# RFID-Lock.net
KiCad netlist of a schematic drawn in EAGLE
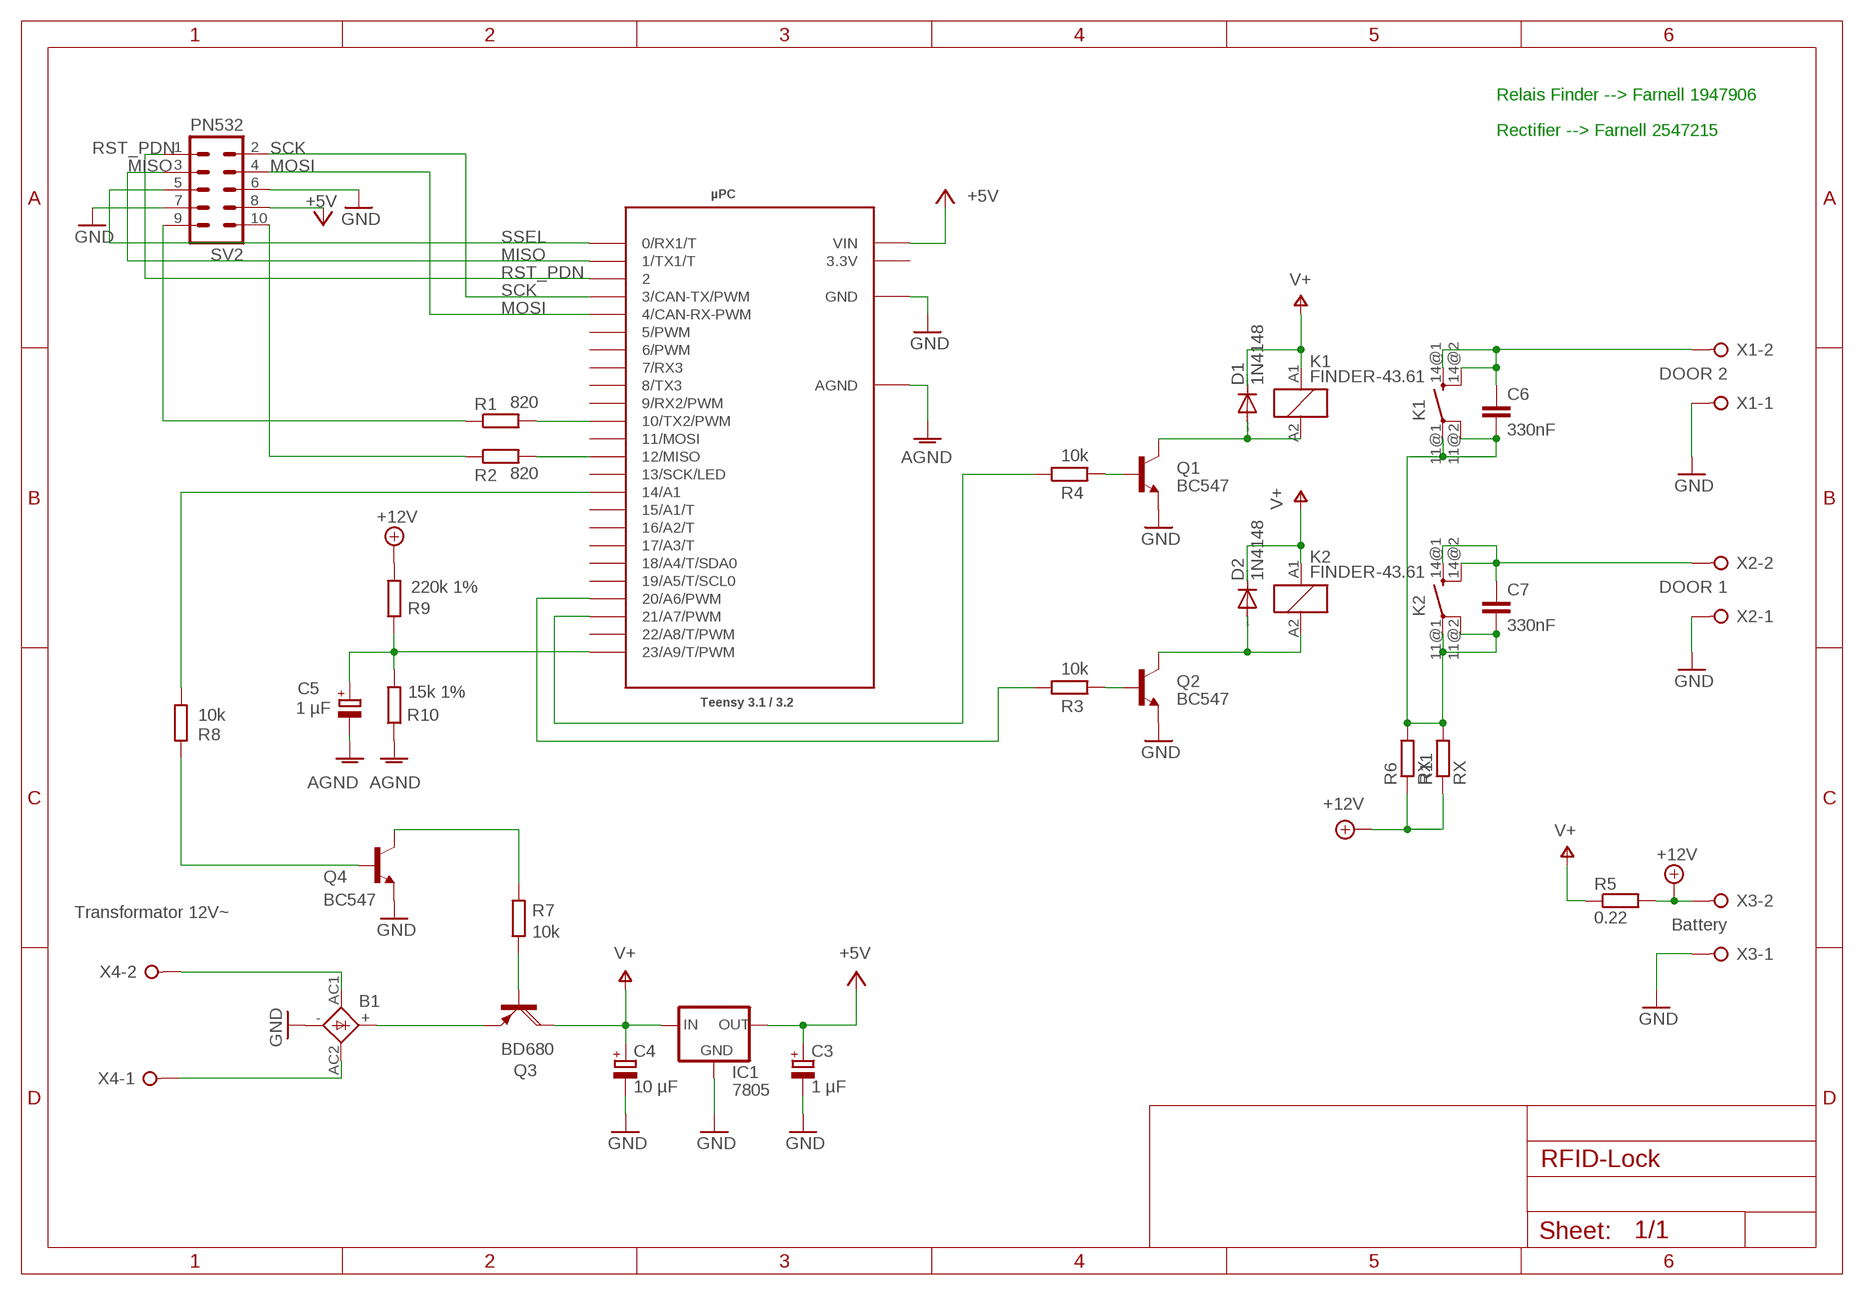
[diagram p0: schematic, sheet 1]

(export (version "E")
  (design (tool "Eeschema 10.0.6"))
  (components
    (comp (ref "B1")
      (value "GBPC6")
      (footprint "eagle-import:GBPC6")
      (libsource (lib "eagle-import") (part "GBPC6"))
    )
    (comp (ref "C3")
      (value "1 µF")
      (footprint "eagle-import:E2,5-5")
      (libsource (lib "eagle-import") (part "CPOL-EUE2.5-5"))
    )
    (comp (ref "C4")
      (value "10 µF")
      (footprint "eagle-import:E2,5-5")
      (libsource (lib "eagle-import") (part "CPOL-EUE2.5-5"))
    )
    (comp (ref "C5")
      (value "1 µF")
      (footprint "eagle-import:E2,5-5")
      (libsource (lib "eagle-import") (part "CPOL-EUE2.5-5"))
    )
    (comp (ref "C6")
      (value "330nF")
      (footprint "eagle-import:C5B4.5")
      (libsource (lib "eagle-import") (part "C5/4.5"))
    )
    (comp (ref "C7")
      (value "330nF")
      (footprint "eagle-import:C5B4.5")
      (libsource (lib "eagle-import") (part "C5/4.5"))
    )
    (comp (ref "D1")
      (value "1N4148")
      (footprint "eagle-import:DO35-7")
      (libsource (lib "eagle-import") (part "1N4148DO35-7"))
    )
    (comp (ref "D2")
      (value "1N4148")
      (footprint "eagle-import:DO35-7")
      (libsource (lib "eagle-import") (part "1N4148DO35-7"))
    )
    (comp (ref "IC1")
      (value "7805")
      (footprint "eagle-import:78XXS")
      (libsource (lib "eagle-import") (part "78XXS"))
    )
    (comp (ref "K1")
      (value "FINDER-43.61")
      (footprint "eagle-import:FINDER-43.61")
      (libsource (lib "eagle-import") (part "FINDER-43.61"))
    )
    (comp (ref "K2")
      (value "FINDER-43.61")
      (footprint "eagle-import:FINDER-43.61")
      (libsource (lib "eagle-import") (part "FINDER-43.61"))
    )
    (comp (ref "Q1")
      (value "BC547")
      (footprint "eagle-import:TO92")
      (libsource (lib "eagle-import") (part "BC547"))
    )
    (comp (ref "Q2")
      (value "BC547")
      (footprint "eagle-import:TO92")
      (libsource (lib "eagle-import") (part "BC547"))
    )
    (comp (ref "Q3")
      (value "BD680")
      (footprint "eagle-import:TO126AV")
      (libsource (lib "eagle-import") (part "BD680"))
    )
    (comp (ref "Q4")
      (value "BC547")
      (footprint "eagle-import:TO92")
      (libsource (lib "eagle-import") (part "BC547"))
    )
    (comp (ref "R1")
      (value "820")
      (footprint "eagle-import:0204_7")
      (libsource (lib "eagle-import") (part "R-EU_0204/7"))
    )
    (comp (ref "R2")
      (value "820")
      (footprint "eagle-import:0204_7")
      (libsource (lib "eagle-import") (part "R-EU_0204/7"))
    )
    (comp (ref "R3")
      (value "10k")
      (footprint "eagle-import:0204_7")
      (libsource (lib "eagle-import") (part "R-EU_0204/7"))
    )
    (comp (ref "R4")
      (value "10k")
      (footprint "eagle-import:0204_7")
      (libsource (lib "eagle-import") (part "R-EU_0204/7"))
    )
    (comp (ref "R5")
      (value "0.22")
      (footprint "eagle-import:0204_7")
      (libsource (lib "eagle-import") (part "resistor_R-EU_0204/7"))
    )
    (comp (ref "R6")
      (value "RX")
      (footprint "eagle-import:P0613_15")
      (libsource (lib "eagle-import") (part "resistor_R-EU_0613/15"))
    )
    (comp (ref "R7")
      (value "10k")
      (footprint "eagle-import:0204_7")
      (libsource (lib "eagle-import") (part "R-EU_0204/7"))
    )
    (comp (ref "R8")
      (value "10k")
      (footprint "eagle-import:0204_7")
      (libsource (lib "eagle-import") (part "R-EU_0204/7"))
    )
    (comp (ref "R9")
      (value "220k 1%")
      (footprint "eagle-import:0204_7")
      (libsource (lib "eagle-import") (part "R-EU_0204/7"))
    )
    (comp (ref "R10")
      (value "15k 1%")
      (footprint "eagle-import:0204_7")
      (libsource (lib "eagle-import") (part "R-EU_0204/7"))
    )
    (comp (ref "R11")
      (value "RX")
      (footprint "eagle-import:P0613_15")
      (libsource (lib "eagle-import") (part "resistor_R-EU_0613/15"))
    )
    (comp (ref "SV2")
      (value "PN532")
      (footprint "eagle-import:MA05-2")
      (libsource (lib "eagle-import") (part "MA05-2"))
    )
    (comp (ref "X1")
      (value "DOOR 2")
      (footprint "eagle-import:W237-132")
      (libsource (lib "eagle-import") (part "W237-02P"))
    )
    (comp (ref "X2")
      (value "DOOR 1")
      (footprint "eagle-import:W237-132")
      (libsource (lib "eagle-import") (part "W237-02P"))
    )
    (comp (ref "X3")
      (value "Battery")
      (footprint "eagle-import:W237-132")
      (libsource (lib "eagle-import") (part "W237-02P"))
    )
    (comp (ref "X4")
      (value "Transformator 12V~")
      (footprint "eagle-import:W237-132")
      (libsource (lib "eagle-import") (part "W237-02P"))
    )
    (comp (ref "µPC")
      (value "Teensy 3.1 / 3.2")
      (footprint "eagle-import:TEENSY3-DIL")
      (libsource (lib "eagle-import") (part "TEENSY_3.1_DIL"))
    )
  )
  (nets
    (net (code "1") (name "+5V") (class "Default")
      (node (ref "C3") (pin "+") (pinfunction "+_+") (pintype "passive"))
      (node (ref "IC1") (pin "OUT") (pinfunction "OUT_OUT") (pintype "passive"))
      (node (ref "SV2") (pin "8") (pinfunction "8_8") (pintype "passive"))
      (node (ref "µPC") (pin "VIN") (pinfunction "VIN_VIN") (pintype "power_in"))
    )
    (net (code "2") (name "+12V") (class "Default")
      (node (ref "R11") (pin "1") (pinfunction "1_1") (pintype "passive"))
      (node (ref "R5") (pin "2") (pinfunction "2_2") (pintype "passive"))
      (node (ref "R6") (pin "1") (pinfunction "1_1") (pintype "passive"))
      (node (ref "R9") (pin "2") (pinfunction "2_2") (pintype "passive"))
      (node (ref "X3") (pin "2") (pinfunction "KL_2") (pintype "passive"))
    )
    (net (code "3") (name "/3.3V") (class "Default")
      (node (ref "µPC") (pin "3.3V") (pinfunction "3.3V_3.3V") (pintype "power_in"))
    )
    (net (code "4") (name "/MISO") (class "Default")
      (node (ref "SV2") (pin "3") (pinfunction "3_3") (pintype "passive"))
      (node (ref "µPC") (pin "1") (pinfunction "1/TX1/T_1") (pintype "bidirectional"))
    )
    (net (code "5") (name "/MOSI") (class "Default")
      (node (ref "SV2") (pin "4") (pinfunction "4_4") (pintype "passive"))
      (node (ref "µPC") (pin "4") (pinfunction "4/CAN-RX-PWM_4") (pintype "bidirectional"))
    )
    (net (code "6") (name "/RST_PDN") (class "Default")
      (node (ref "SV2") (pin "1") (pinfunction "1_1") (pintype "passive"))
      (node (ref "µPC") (pin "2") (pinfunction "2_2") (pintype "bidirectional"))
    )
    (net (code "7") (name "/SCK") (class "Default")
      (node (ref "SV2") (pin "2") (pinfunction "2_2") (pintype "passive"))
      (node (ref "µPC") (pin "3") (pinfunction "3/CAN-TX/PWM_3") (pintype "bidirectional"))
    )
    (net (code "8") (name "/SSEL") (class "Default")
      (node (ref "SV2") (pin "5") (pinfunction "5_5") (pintype "passive"))
      (node (ref "µPC") (pin "0") (pinfunction "0/RX1/T_0") (pintype "bidirectional"))
    )
    (net (code "9") (name "AGND") (class "Default")
      (node (ref "C5") (pin "-") (pinfunction "-_-") (pintype "passive"))
      (node (ref "R10") (pin "1") (pinfunction "1_1") (pintype "passive"))
      (node (ref "µPC") (pin "AGND") (pinfunction "AGND_AGND") (pintype "power_in"))
    )
    (net (code "10") (name "GND") (class "Default")
      (node (ref "B1") (pin "-") (pinfunction "-_-") (pintype "passive"))
      (node (ref "C3") (pin "-") (pinfunction "-_-") (pintype "passive"))
      (node (ref "C4") (pin "-") (pinfunction "-_-") (pintype "passive"))
      (node (ref "IC1") (pin "GND") (pinfunction "GND_GND") (pintype "input"))
      (node (ref "Q1") (pin "1") (pinfunction "E_1") (pintype "passive"))
      (node (ref "Q2") (pin "1") (pinfunction "E_1") (pintype "passive"))
      (node (ref "Q4") (pin "1") (pinfunction "E_1") (pintype "passive"))
      (node (ref "SV2") (pin "6") (pinfunction "6_6") (pintype "passive"))
      (node (ref "SV2") (pin "7") (pinfunction "7_7") (pintype "passive"))
      (node (ref "X1") (pin "1") (pinfunction "KL_1") (pintype "passive"))
      (node (ref "X2") (pin "1") (pinfunction "KL_1") (pintype "passive"))
      (node (ref "X3") (pin "1") (pinfunction "KL_1") (pintype "passive"))
      (node (ref "µPC") (pin "GND") (pinfunction "GND_GND") (pintype "power_in"))
    )
    (net (code "11") (name "Net-(B1-Pad+)") (class "Default")
      (node (ref "B1") (pin "+") (pinfunction "+_+") (pintype "passive"))
      (node (ref "Q3") (pin "E") (pinfunction "E_E") (pintype "passive"))
    )
    (net (code "12") (name "Net-(K1A-PA)") (class "Default")
      (node (ref "C6") (pin "2") (pinfunction "2_2") (pintype "passive"))
      (node (ref "C7") (pin "2") (pinfunction "2_2") (pintype "passive"))
      (node (ref "K1") (pin "11@1") (pinfunction "PA_11@1") (pintype "passive"))
      (node (ref "K1") (pin "11@2") (pinfunction "PB_11@2") (pintype "passive"))
      (node (ref "K2") (pin "11@1") (pinfunction "PA_11@1") (pintype "passive"))
      (node (ref "K2") (pin "11@2") (pinfunction "PB_11@2") (pintype "passive"))
      (node (ref "R11") (pin "2") (pinfunction "2_2") (pintype "passive"))
      (node (ref "R6") (pin "2") (pinfunction "2_2") (pintype "passive"))
    )
    (net (code "13") (name "Net-(K1A-SA)") (class "Default")
      (node (ref "C6") (pin "1") (pinfunction "1_1") (pintype "passive"))
      (node (ref "K1") (pin "14@1") (pinfunction "SA_14@1") (pintype "passive"))
      (node (ref "K1") (pin "14@2") (pinfunction "SB_14@2") (pintype "passive"))
      (node (ref "X1") (pin "2") (pinfunction "KL_2") (pintype "passive"))
    )
    (net (code "14") (name "Net-(K1B-2)") (class "Default")
      (node (ref "D1") (pin "A") (pinfunction "A_A") (pintype "passive"))
      (node (ref "K1") (pin "A2") (pinfunction "2_A2") (pintype "passive"))
      (node (ref "Q1") (pin "3") (pinfunction "C_3") (pintype "passive"))
    )
    (net (code "15") (name "Net-(K2A-SA)") (class "Default")
      (node (ref "C7") (pin "1") (pinfunction "1_1") (pintype "passive"))
      (node (ref "K2") (pin "14@1") (pinfunction "SA_14@1") (pintype "passive"))
      (node (ref "K2") (pin "14@2") (pinfunction "SB_14@2") (pintype "passive"))
      (node (ref "X2") (pin "2") (pinfunction "KL_2") (pintype "passive"))
    )
    (net (code "16") (name "Net-(K2B-2)") (class "Default")
      (node (ref "D2") (pin "A") (pinfunction "A_A") (pintype "passive"))
      (node (ref "K2") (pin "A2") (pinfunction "2_A2") (pintype "passive"))
      (node (ref "Q2") (pin "3") (pinfunction "C_3") (pintype "passive"))
    )
    (net (code "17") (name "Net-(Q1-B)") (class "Default")
      (node (ref "Q1") (pin "2") (pinfunction "B_2") (pintype "passive"))
      (node (ref "R4") (pin "2") (pinfunction "2_2") (pintype "passive"))
    )
    (net (code "18") (name "Net-(Q2-B)") (class "Default")
      (node (ref "Q2") (pin "2") (pinfunction "B_2") (pintype "passive"))
      (node (ref "R3") (pin "2") (pinfunction "2_2") (pintype "passive"))
    )
    (net (code "19") (name "Net-(Q3-PadB)") (class "Default")
      (node (ref "Q3") (pin "B") (pinfunction "B_B") (pintype "passive"))
      (node (ref "R7") (pin "1") (pinfunction "1_1") (pintype "passive"))
    )
    (net (code "20") (name "Net-(Q4-B)") (class "Default")
      (node (ref "Q4") (pin "2") (pinfunction "B_2") (pintype "passive"))
      (node (ref "R8") (pin "1") (pinfunction "1_1") (pintype "passive"))
    )
    (net (code "21") (name "Net-(Q4-C)") (class "Default")
      (node (ref "Q4") (pin "3") (pinfunction "C_3") (pintype "passive"))
      (node (ref "R7") (pin "2") (pinfunction "2_2") (pintype "passive"))
    )
    (net (code "22") (name "Net-(R1-Pad1)") (class "Default")
      (node (ref "R1") (pin "1") (pinfunction "1_1") (pintype "passive"))
      (node (ref "SV2") (pin "9") (pinfunction "9_9") (pintype "passive"))
    )
    (net (code "23") (name "Net-(R2-Pad1)") (class "Default")
      (node (ref "R2") (pin "1") (pinfunction "1_1") (pintype "passive"))
      (node (ref "SV2") (pin "10") (pinfunction "10_10") (pintype "passive"))
    )
    (net (code "24") (name "Net-(X4A-KL)") (class "Default")
      (node (ref "B1") (pin "AC2") (pinfunction "AC2_AC2") (pintype "passive"))
      (node (ref "X4") (pin "1") (pinfunction "KL_1") (pintype "passive"))
    )
    (net (code "25") (name "Net-(X4B-KL)") (class "Default")
      (node (ref "B1") (pin "AC1") (pinfunction "AC1_AC1") (pintype "passive"))
      (node (ref "X4") (pin "2") (pinfunction "KL_2") (pintype "passive"))
    )
    (net (code "26") (name "Net-(µPC-10{slash}TX2{slash}PWM)") (class "Default")
      (node (ref "R1") (pin "2") (pinfunction "2_2") (pintype "passive"))
      (node (ref "µPC") (pin "10") (pinfunction "10/TX2/PWM_10") (pintype "bidirectional"))
    )
    (net (code "27") (name "Net-(µPC-12{slash}MISO)") (class "Default")
      (node (ref "R2") (pin "2") (pinfunction "2_2") (pintype "passive"))
      (node (ref "µPC") (pin "12") (pinfunction "12/MISO_12") (pintype "bidirectional"))
    )
    (net (code "28") (name "Net-(µPC-14{slash}A1)") (class "Default")
      (node (ref "R8") (pin "2") (pinfunction "2_2") (pintype "passive"))
      (node (ref "µPC") (pin "14/A0") (pinfunction "14/A1_14/A0") (pintype "bidirectional"))
    )
    (net (code "29") (name "Net-(µPC-20{slash}A6{slash}PWM)") (class "Default")
      (node (ref "R3") (pin "1") (pinfunction "1_1") (pintype "passive"))
      (node (ref "µPC") (pin "20/A6") (pinfunction "20/A6/PWM_20/A6") (pintype "bidirectional"))
    )
    (net (code "30") (name "Net-(µPC-21{slash}A7{slash}PWM)") (class "Default")
      (node (ref "R4") (pin "1") (pinfunction "1_1") (pintype "passive"))
      (node (ref "µPC") (pin "21/A7") (pinfunction "21/A7/PWM_21/A7") (pintype "bidirectional"))
    )
    (net (code "31") (name "Net-(µPC-23{slash}A9{slash}T{slash}PWM)") (class "Default")
      (node (ref "C5") (pin "+") (pinfunction "+_+") (pintype "passive"))
      (node (ref "R10") (pin "2") (pinfunction "2_2") (pintype "passive"))
      (node (ref "R9") (pin "1") (pinfunction "1_1") (pintype "passive"))
      (node (ref "µPC") (pin "23/A9") (pinfunction "23/A9/T/PWM_23/A9") (pintype "bidirectional"))
    )
    (net (code "32") (name "V+") (class "Default")
      (node (ref "C4") (pin "+") (pinfunction "+_+") (pintype "passive"))
      (node (ref "D1") (pin "C") (pinfunction "C_C") (pintype "passive"))
      (node (ref "D2") (pin "C") (pinfunction "C_C") (pintype "passive"))
      (node (ref "IC1") (pin "IN") (pinfunction "IN_IN") (pintype "input"))
      (node (ref "K1") (pin "A1") (pinfunction "1_A1") (pintype "passive"))
      (node (ref "K2") (pin "A1") (pinfunction "1_A1") (pintype "passive"))
      (node (ref "Q3") (pin "C") (pinfunction "C_C") (pintype "passive"))
      (node (ref "R5") (pin "1") (pinfunction "1_1") (pintype "passive"))
    )
    (net (code "33") (name "unconnected-(µPC-5{slash}PWM-Pad5)") (class "Default")
      (node (ref "µPC") (pin "5") (pinfunction "5/PWM_5") (pintype "bidirectional"))
    )
    (net (code "34") (name "unconnected-(µPC-6{slash}PWM-Pad6)") (class "Default")
      (node (ref "µPC") (pin "6") (pinfunction "6/PWM_6") (pintype "bidirectional"))
    )
    (net (code "35") (name "unconnected-(µPC-7{slash}RX3-Pad7)") (class "Default")
      (node (ref "µPC") (pin "7") (pinfunction "7/RX3_7") (pintype "bidirectional"))
    )
    (net (code "36") (name "unconnected-(µPC-8{slash}TX3-Pad8)") (class "Default")
      (node (ref "µPC") (pin "8") (pinfunction "8/TX3_8") (pintype "bidirectional"))
    )
    (net (code "37") (name "unconnected-(µPC-9{slash}RX2{slash}PWM-Pad9)") (class "Default")
      (node (ref "µPC") (pin "9") (pinfunction "9/RX2/PWM_9") (pintype "bidirectional"))
    )
    (net (code "38") (name "unconnected-(µPC-11{slash}MOSI-Pad11)") (class "Default")
      (node (ref "µPC") (pin "11") (pinfunction "11/MOSI_11") (pintype "bidirectional"))
    )
    (net (code "39") (name "unconnected-(µPC-13{slash}SCK{slash}LED-Pad13)") (class "Default")
      (node (ref "µPC") (pin "13") (pinfunction "13/SCK/LED_13") (pintype "bidirectional"))
    )
    (net (code "40") (name "unconnected-(µPC-15{slash}A1{slash}T-Pad15{slash}A1)") (class "Default")
      (node (ref "µPC") (pin "15/A1") (pinfunction "15/A1/T_15/A1") (pintype "bidirectional"))
    )
    (net (code "41") (name "unconnected-(µPC-16{slash}A2{slash}T-Pad16{slash}A2)") (class "Default")
      (node (ref "µPC") (pin "16/A2") (pinfunction "16/A2/T_16/A2") (pintype "bidirectional"))
    )
    (net (code "42") (name "unconnected-(µPC-17{slash}A3{slash}T-Pad17{slash}A3)") (class "Default")
      (node (ref "µPC") (pin "17/A3") (pinfunction "17/A3/T_17/A3") (pintype "bidirectional"))
    )
    (net (code "43") (name "unconnected-(µPC-18{slash}A4{slash}T{slash}SDA0-Pad18{slash}A4)") (class "Default")
      (node (ref "µPC") (pin "18/A4") (pinfunction "18/A4/T/SDA0_18/A4") (pintype "bidirectional"))
    )
    (net (code "44") (name "unconnected-(µPC-19{slash}A5{slash}T{slash}SCL0-Pad19{slash}A5)") (class "Default")
      (node (ref "µPC") (pin "19/A5") (pinfunction "19/A5/T/SCL0_19/A5") (pintype "bidirectional"))
    )
    (net (code "45") (name "unconnected-(µPC-22{slash}A8{slash}T{slash}PWM-Pad22{slash}A8)") (class "Default")
      (node (ref "µPC") (pin "22/A8") (pinfunction "22/A8/T/PWM_22/A8") (pintype "bidirectional"))
    )
  )
)
